# Angular_Encoder.net
KiCad netlist of a schematic drawn in Altium Designer
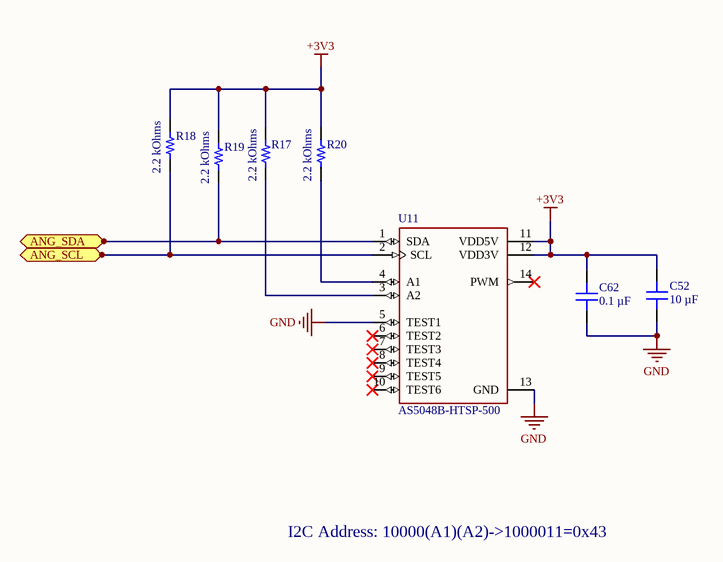
[diagram p0: Angular_Encoder.SchDoc]

(export (version "E")
  (design (tool "Eeschema 10.0.6"))
  (components
    (comp (ref "C52")
      (value "10 µF")
      (footprint "CAP 0603_1608")
      (description "CAP CER 10UF 16V X5R 0603")
      (fields
        (field (name "PART NUMBER") "CC0603MRX5R7BB106")
        (field (name "CAPACITANCE") "10 µF")
        (field (name "MANUFACTURER") "Yageo")
      )
      (libsource (lib "Celestial Altium Library - altium_library") (part "Capacitor"))
    )
    (comp (ref "C62")
      (value "0.1 µF")
      (footprint "CAP 0402_1005")
      (description "CAP CER 0.1UF 6.3V X5R 0402")
      (fields
        (field (name "PART NUMBER") "C0402C104M9PAC7867")
        (field (name "CAPACITANCE") "0.1 µF")
        (field (name "MANUFACTURER") "KEMET")
      )
      (libsource (lib "Celestial Altium Library - altium_library") (part "Capacitor"))
    )
    (comp (ref "R17")
      (value "2.2 kOhms")
      (footprint "YAGEO RES 0402_1005")
      (description "RES 2.2K OHM 1% 1/16W 0402")
      (fields (field (name "PART NUMBER") "RC0402FR-072K2L") (field (name "MANUFACTURER") "Yageo"))
      (libsource (lib "Celestial Altium Library - altium_library") (part "Resistor"))
    )
    (comp (ref "R18")
      (value "2.2 kOhms")
      (footprint "YAGEO RES 0402_1005")
      (description "RES 2.2K OHM 1% 1/16W 0402")
      (fields (field (name "PART NUMBER") "RC0402FR-072K2L") (field (name "MANUFACTURER") "Yageo"))
      (libsource (lib "Celestial Altium Library - altium_library") (part "Resistor"))
    )
    (comp (ref "R19")
      (value "2.2 kOhms")
      (footprint "YAGEO RES 0402_1005")
      (description "RES 2.2K OHM 1% 1/16W 0402")
      (fields (field (name "PART NUMBER") "RC0402FR-072K2L") (field (name "MANUFACTURER") "Yageo"))
      (libsource (lib "Celestial Altium Library - altium_library") (part "Resistor"))
    )
    (comp (ref "R20")
      (value "2.2 kOhms")
      (footprint "YAGEO RES 0402_1005")
      (description "RES 2.2K OHM 1% 1/16W 0402")
      (fields (field (name "PART NUMBER") "RC0402FR-072K2L") (field (name "MANUFACTURER") "Yageo"))
      (libsource (lib "Celestial Altium Library - altium_library") (part "Resistor"))
    )
    (comp (ref "U11")
      (value "AS5048B-HTSP-500")
      (footprint "AS5048B-HTSP-500")
      (description "Hall Effect Sensor Angle External Magnet, Not Included Gull Wing")
      (fields (field (name "MANUFACTURER") "ams-OSRAM USA INC."))
      (libsource (lib "PCB_Lib") (part "AS5048B-HTSP-500"))
    )
  )
  (nets
    (net (code "1") (name "+3V3") (class "Default")
      (node (ref "C52") (pin "2") (pinfunction "2_2") (pintype "passive"))
      (node (ref "C62") (pin "2") (pinfunction "2_2") (pintype "passive"))
      (node (ref "R17") (pin "2") (pinfunction "2_2") (pintype "passive"))
      (node (ref "R18") (pin "2") (pinfunction "2_2") (pintype "passive"))
      (node (ref "R19") (pin "2") (pinfunction "2_2") (pintype "passive"))
      (node (ref "R20") (pin "2") (pinfunction "2_2") (pintype "passive"))
      (node (ref "U11") (pin "11") (pinfunction "VDD5V_11") (pintype "power_in"))
      (node (ref "U11") (pin "12") (pinfunction "VDD3V_12") (pintype "power_in"))
    )
    (net (code "2") (name "/ANG_SCL") (class "Default")
      (node (ref "R18") (pin "1") (pinfunction "1_1") (pintype "passive"))
      (node (ref "U11") (pin "2") (pinfunction "SCL_2") (pintype "input"))
    )
    (net (code "3") (name "/ANG_SDA") (class "Default")
      (node (ref "R19") (pin "1") (pinfunction "1_1") (pintype "passive"))
      (node (ref "U11") (pin "1") (pinfunction "SDA_1") (pintype "bidirectional"))
    )
    (net (code "4") (name "GND") (class "Default")
      (node (ref "C52") (pin "1") (pinfunction "1_1") (pintype "passive"))
      (node (ref "C62") (pin "1") (pinfunction "1_1") (pintype "passive"))
      (node (ref "U11") (pin "13") (pinfunction "GND_13") (pintype "passive"))
      (node (ref "U11") (pin "5") (pinfunction "TEST1_5") (pintype "bidirectional"))
    )
    (net (code "5") (name "Net-(U11-A1)") (class "Default")
      (node (ref "R20") (pin "1") (pinfunction "1_1") (pintype "passive"))
      (node (ref "U11") (pin "4") (pinfunction "A1_4") (pintype "bidirectional"))
    )
    (net (code "6") (name "Net-(U11-A2)") (class "Default")
      (node (ref "R17") (pin "1") (pinfunction "1_1") (pintype "passive"))
      (node (ref "U11") (pin "3") (pinfunction "A2_3") (pintype "bidirectional"))
    )
    (net (code "7") (name "unconnected-(U11-PWM-Pad14)") (class "Default")
      (node (ref "U11") (pin "14") (pinfunction "PWM_14") (pintype "output+no_connect"))
    )
    (net (code "8") (name "unconnected-(U11-TEST2-Pad6)") (class "Default")
      (node (ref "U11") (pin "6") (pinfunction "TEST2_6") (pintype "bidirectional+no_connect"))
    )
    (net (code "9") (name "unconnected-(U11-TEST3-Pad7)") (class "Default")
      (node (ref "U11") (pin "7") (pinfunction "TEST3_7") (pintype "bidirectional+no_connect"))
    )
    (net (code "10") (name "unconnected-(U11-TEST4-Pad8)") (class "Default")
      (node (ref "U11") (pin "8") (pinfunction "TEST4_8") (pintype "bidirectional+no_connect"))
    )
    (net (code "11") (name "unconnected-(U11-TEST5-Pad9)") (class "Default")
      (node (ref "U11") (pin "9") (pinfunction "TEST5_9") (pintype "bidirectional+no_connect"))
    )
    (net (code "12") (name "unconnected-(U11-TEST6-Pad10)") (class "Default")
      (node (ref "U11") (pin "10") (pinfunction "TEST6_10") (pintype "bidirectional+no_connect"))
    )
  )
)
